# MotorDriver.net
KiCad netlist of a schematic drawn in EAGLE
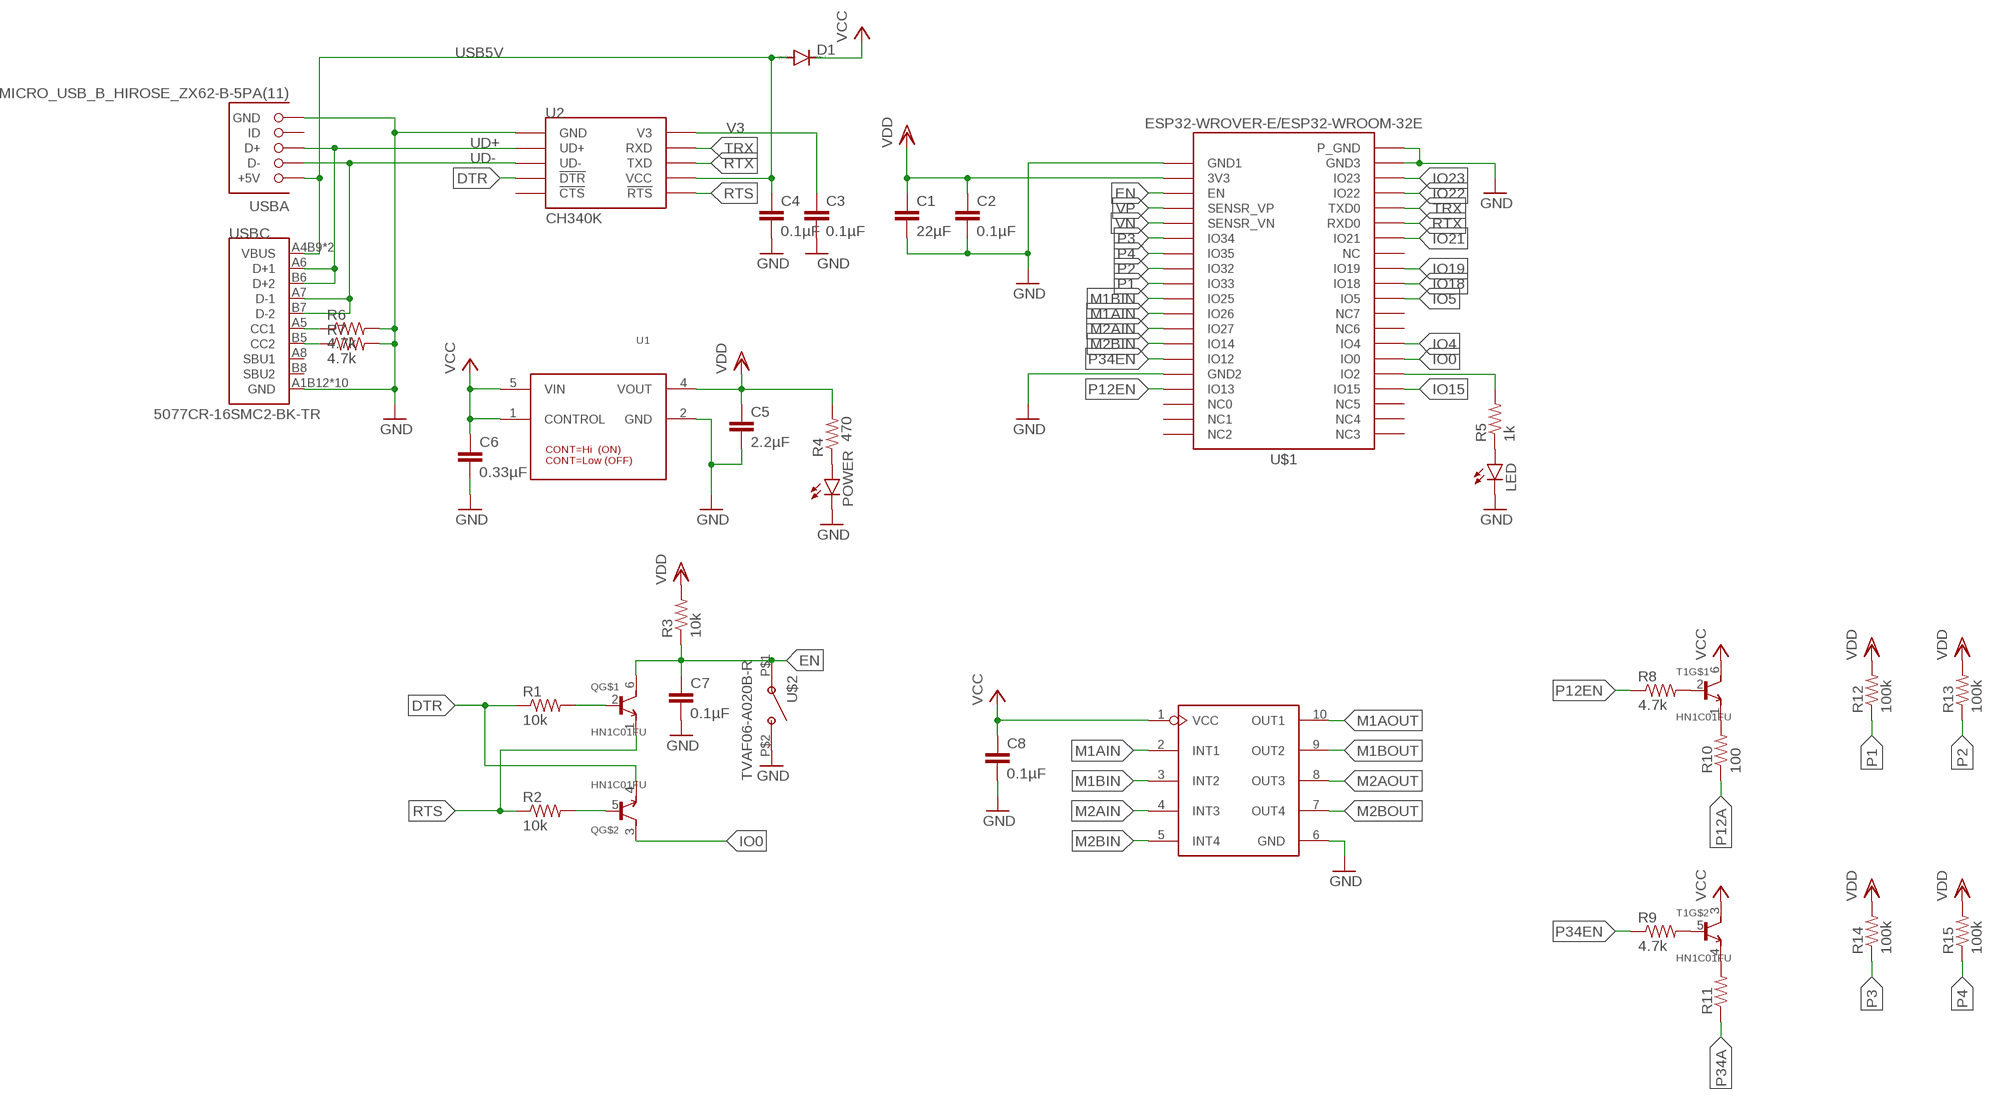
[diagram p0: schematic, sheet 1]

(export (version "E")
  (design (tool "Eeschema 10.0.6"))
  (components
    (comp (ref "C1")
      (value "22µF")
      (footprint "eagle-import:C0603K")
      (libsource (lib "eagle-import") (part "C-EUC0603K"))
    )
    (comp (ref "C2")
      (value "0.1µF")
      (footprint "eagle-import:C0603K")
      (libsource (lib "eagle-import") (part "C-EUC0603K"))
    )
    (comp (ref "C3")
      (value "0.1µF")
      (footprint "eagle-import:C0603K")
      (libsource (lib "eagle-import") (part "C-EUC0603K"))
    )
    (comp (ref "C4")
      (value "0.1µF")
      (footprint "eagle-import:C0603K")
      (libsource (lib "eagle-import") (part "C-EUC0603K"))
    )
    (comp (ref "C5")
      (value "2.2µF")
      (footprint "eagle-import:C0603K")
      (libsource (lib "eagle-import") (part "C-EUC0603K"))
    )
    (comp (ref "C6")
      (value "0.33µF")
      (footprint "eagle-import:C0603K")
      (libsource (lib "eagle-import") (part "C-EUC0603K"))
    )
    (comp (ref "C7")
      (value "0.1µF")
      (footprint "eagle-import:C0603K")
      (libsource (lib "eagle-import") (part "C-EUC0603K"))
    )
    (comp (ref "C8")
      (value "0.1µF")
      (footprint "eagle-import:C0603")
      (libsource (lib "eagle-import") (part "C-EUC0603"))
    )
    (comp (ref "D1")
      (value "DIODE-SOD123")
      (footprint "eagle-import:SOD123")
      (libsource (lib "eagle-import") (part "DIODE-SOD123"))
    )
    (comp (ref "LED")
      (value "LEDCHIPLED_0603")
      (footprint "eagle-import:CHIPLED_0603")
      (libsource (lib "eagle-import") (part "LEDCHIPLED_0603"))
    )
    (comp (ref "POWER")
      (value "LEDCHIPLED_0603")
      (footprint "eagle-import:CHIPLED_0603")
      (libsource (lib "eagle-import") (part "LEDCHIPLED_0603"))
    )
    (comp (ref "Q")
      (value "HN1C01FU")
      (footprint "eagle-import:SOT-363")
      (libsource (lib "eagle-import") (part "HN1C01FU"))
    )
    (comp (ref "R1")
      (value "10k")
      (footprint "eagle-import:R0603")
      (libsource (lib "eagle-import") (part "R-US_R0603"))
    )
    (comp (ref "R2")
      (value "10k")
      (footprint "eagle-import:R0603")
      (libsource (lib "eagle-import") (part "R-US_R0603"))
    )
    (comp (ref "R3")
      (value "10k")
      (footprint "eagle-import:R0603")
      (libsource (lib "eagle-import") (part "R-US_R0603"))
    )
    (comp (ref "R4")
      (value "470")
      (footprint "eagle-import:R0603")
      (libsource (lib "eagle-import") (part "R-US_R0603"))
    )
    (comp (ref "R5")
      (value "1k")
      (footprint "eagle-import:R0603")
      (libsource (lib "eagle-import") (part "R-US_R0603"))
    )
    (comp (ref "R6")
      (value "4.7k")
      (footprint "eagle-import:R0603")
      (libsource (lib "eagle-import") (part "R-US_R0603"))
    )
    (comp (ref "R7")
      (value "4.7k")
      (footprint "eagle-import:R0603")
      (libsource (lib "eagle-import") (part "R-US_R0603"))
    )
    (comp (ref "R8")
      (value "4.7k")
      (footprint "eagle-import:R0603")
      (libsource (lib "eagle-import") (part "R-US_R0603"))
    )
    (comp (ref "R9")
      (value "4.7k")
      (footprint "eagle-import:R0603")
      (libsource (lib "eagle-import") (part "R-US_R0603"))
    )
    (comp (ref "R10")
      (value "100")
      (footprint "eagle-import:R0603")
      (libsource (lib "eagle-import") (part "R-US_R0603"))
    )
    (comp (ref "R11")
      (value "R-US_R0603")
      (footprint "eagle-import:R0603")
      (libsource (lib "eagle-import") (part "R-US_R0603"))
    )
    (comp (ref "R12")
      (value "100k")
      (footprint "eagle-import:R0603")
      (libsource (lib "eagle-import") (part "R-US_R0603"))
    )
    (comp (ref "R13")
      (value "100k")
      (footprint "eagle-import:R0603")
      (libsource (lib "eagle-import") (part "R-US_R0603"))
    )
    (comp (ref "R14")
      (value "100k")
      (footprint "eagle-import:R0603")
      (libsource (lib "eagle-import") (part "R-US_R0603"))
    )
    (comp (ref "R15")
      (value "100k")
      (footprint "eagle-import:R0603")
      (libsource (lib "eagle-import") (part "R-US_R0603"))
    )
    (comp (ref "T1")
      (value "HN1C01FU")
      (footprint "eagle-import:SOT-363")
      (libsource (lib "eagle-import") (part "HN1C01FU"))
    )
    (comp (ref "U$1")
      (value "ESP32-WROVER-E/ESP32-WROOM-32E")
      (footprint "eagle-import:ESP32-WROVER-E_ESP32-WROOM-32E")
      (libsource (lib "eagle-import") (part "ESP32-WROVER-E/ESP32-WROOM-32E"))
    )
    (comp (ref "U$2")
      (value "TVAF06-A020B-R")
      (footprint "eagle-import:TVAF06-A020B-R")
      (libsource (lib "eagle-import") (part "TVAF06-A020B-R"))
    )
    (comp (ref "U1")
      (value "I-10673_NJM2884U1-33")
      (footprint "eagle-import:NJM2884U1-33")
      (libsource (lib "eagle-import") (part "I-10673_NJM2884U1-33"))
    )
    (comp (ref "U2")
      (value "CH340K")
      (footprint "eagle-import:ESSOP-10")
      (libsource (lib "eagle-import") (part "CH340K"))
    )
    (comp (ref "U3")
      (value "DRIVER-LV8548MC-AH(SOIC10)")
      (footprint "eagle-import:SOIC10-1.0-5X4MM")
      (fields (field (name "MF") "ON Semiconductor") (field (name "MP") "LV8548MC-AH"))
      (libsource (lib "eagle-import") (part "DRIVER-LV8548MC-AH(SOIC10)"))
    )
    (comp (ref "USBA")
      (value "MICRO_USB_B_HIROSE_ZX62-B-5PA(11)")
      (footprint "eagle-import:USB_MICRO_B-HIROSE-ZX62-B-5PA(11)")
      (libsource (lib "eagle-import") (part "MICRO_USB_B_HIROSE_ZX62-B-5PA(11)"))
    )
    (comp (ref "USBC")
      (value "5077CR-16SMC2-BK-TR")
      (footprint "eagle-import:5077CR-16SMC2-BK-TR")
      (libsource (lib "eagle-import") (part "5077CR-16SMC2-BK-TR"))
    )
  )
  (nets
    (net (code "1") (name "/UD+") (class "Default")
      (node (ref "U2") (pin "P1") (pinfunction "UD+_P1") (pintype "bidirectional"))
      (node (ref "USBA") (pin "3") (pinfunction "D+_3") (pintype "bidirectional"))
      (node (ref "USBC") (pin "A6") (pinfunction "D+1_A6") (pintype "bidirectional"))
      (node (ref "USBC") (pin "B6") (pinfunction "D+2_B6") (pintype "bidirectional"))
    )
    (net (code "2") (name "/UD-") (class "Default")
      (node (ref "U2") (pin "P2") (pinfunction "UD-_P2") (pintype "bidirectional"))
      (node (ref "USBA") (pin "2") (pinfunction "D-_2") (pintype "bidirectional"))
      (node (ref "USBC") (pin "A7") (pinfunction "D-1_A7") (pintype "bidirectional"))
      (node (ref "USBC") (pin "B7") (pinfunction "D-2_B7") (pintype "bidirectional"))
    )
    (net (code "3") (name "/USB5V") (class "Default")
      (node (ref "C4") (pin "1") (pinfunction "1_1") (pintype "passive"))
      (node (ref "D1") (pin "A") (pinfunction "A_A") (pintype "passive"))
      (node (ref "U2") (pin "P7") (pinfunction "VCC_P7") (pintype "power_in"))
      (node (ref "USBA") (pin "1") (pinfunction "+5V_1") (pintype "bidirectional"))
      (node (ref "USBC") (pin "A4B9") (pinfunction "VBUS_A4B9") (pintype "power_in"))
      (node (ref "USBC") (pin "B4A9") (pinfunction "VBUS_B4A9") (pintype "power_in"))
    )
    (net (code "4") (name "/V3") (class "Default")
      (node (ref "C3") (pin "1") (pinfunction "1_1") (pintype "passive"))
      (node (ref "U2") (pin "P10") (pinfunction "V3_P10") (pintype "power_in"))
    )
    (net (code "5") (name "DTR") (class "Default")
      (node (ref "Q") (pin "4") (pinfunction "E_4") (pintype "bidirectional"))
      (node (ref "R1") (pin "1") (pinfunction "1_1") (pintype "passive"))
      (node (ref "U2") (pin "P4") (pinfunction "~{DTR}_P4") (pintype "bidirectional"))
    )
    (net (code "6") (name "EN") (class "Default")
      (node (ref "C7") (pin "1") (pinfunction "1_1") (pintype "passive"))
      (node (ref "Q") (pin "6") (pinfunction "C_6") (pintype "bidirectional"))
      (node (ref "R3") (pin "1") (pinfunction "1_1") (pintype "passive"))
      (node (ref "U$1") (pin "EN") (pinfunction "EN_EN") (pintype "bidirectional"))
      (node (ref "U$2") (pin "P$1") (pinfunction "A_P$1") (pintype "bidirectional"))
    )
    (net (code "7") (name "GND") (class "Default")
      (node (ref "C1") (pin "2") (pinfunction "2_2") (pintype "passive"))
      (node (ref "C2") (pin "2") (pinfunction "2_2") (pintype "passive"))
      (node (ref "C3") (pin "2") (pinfunction "2_2") (pintype "passive"))
      (node (ref "C4") (pin "2") (pinfunction "2_2") (pintype "passive"))
      (node (ref "C5") (pin "2") (pinfunction "2_2") (pintype "passive"))
      (node (ref "C6") (pin "2") (pinfunction "2_2") (pintype "passive"))
      (node (ref "C7") (pin "2") (pinfunction "2_2") (pintype "passive"))
      (node (ref "C8") (pin "2") (pinfunction "2_2") (pintype "passive"))
      (node (ref "LED") (pin "C") (pinfunction "C_C") (pintype "passive"))
      (node (ref "POWER") (pin "C") (pinfunction "C_C") (pintype "passive"))
      (node (ref "R6") (pin "2") (pinfunction "2_2") (pintype "passive"))
      (node (ref "R7") (pin "2") (pinfunction "2_2") (pintype "passive"))
      (node (ref "U$1") (pin "GND1") (pinfunction "GND1_GND1") (pintype "power_in"))
      (node (ref "U$1") (pin "GND2") (pinfunction "GND2_GND2") (pintype "power_in"))
      (node (ref "U$1") (pin "GND2'") (pinfunction "GND2_GND2'") (pintype "power_in"))
      (node (ref "U$1") (pin "GND3") (pinfunction "GND3_GND3") (pintype "power_in"))
      (node (ref "U$1") (pin "P_GND") (pinfunction "P_GND_P_GND") (pintype "power_in"))
      (node (ref "U$2") (pin "P$2") (pinfunction "B_P$2") (pintype "bidirectional"))
      (node (ref "U1") (pin "2") (pinfunction "GND_2") (pintype "bidirectional"))
      (node (ref "U2") (pin "P0") (pinfunction "GND_P0") (pintype "power_in"))
      (node (ref "U2") (pin "P3") (pinfunction "GND_P3") (pintype "power_in"))
      (node (ref "U3") (pin "6") (pinfunction "GND_6") (pintype "bidirectional"))
      (node (ref "USBA") (pin "5") (pinfunction "GND_5") (pintype "bidirectional"))
      (node (ref "USBC") (pin "A1B12") (pinfunction "GND_A1B12") (pintype "power_in"))
      (node (ref "USBC") (pin "B1A12") (pinfunction "GND_B1A12") (pintype "power_in"))
      (node (ref "USBC") (pin "P$1") (pinfunction "GND_P$1") (pintype "power_in"))
      (node (ref "USBC") (pin "P$2") (pinfunction "GND_P$2") (pintype "power_in"))
      (node (ref "USBC") (pin "P$3") (pinfunction "GND_P$3") (pintype "power_in"))
      (node (ref "USBC") (pin "P$4") (pinfunction "GND_P$4") (pintype "power_in"))
      (node (ref "USBC") (pin "P$5") (pinfunction "GND_P$5") (pintype "power_in"))
      (node (ref "USBC") (pin "P$6") (pinfunction "GND_P$6") (pintype "power_in"))
      (node (ref "USBC") (pin "P$7") (pinfunction "GND_P$7") (pintype "power_in"))
      (node (ref "USBC") (pin "P$8") (pinfunction "GND_P$8") (pintype "power_in"))
    )
    (net (code "8") (name "IO0") (class "Default")
      (node (ref "Q") (pin "3") (pinfunction "C_3") (pintype "bidirectional"))
      (node (ref "U$1") (pin "IO0") (pinfunction "IO0_IO0") (pintype "bidirectional"))
    )
    (net (code "9") (name "IO4") (class "Default")
      (node (ref "U$1") (pin "IO4") (pinfunction "IO4_IO4") (pintype "bidirectional"))
    )
    (net (code "10") (name "IO5") (class "Default")
      (node (ref "U$1") (pin "IO5") (pinfunction "IO5_IO5") (pintype "bidirectional"))
    )
    (net (code "11") (name "IO15") (class "Default")
      (node (ref "U$1") (pin "IO15") (pinfunction "IO15_IO15") (pintype "bidirectional"))
      (node (ref "U$1") (pin "IO15'") (pinfunction "IO15_IO15'") (pintype "bidirectional"))
    )
    (net (code "12") (name "IO18") (class "Default")
      (node (ref "U$1") (pin "IO18") (pinfunction "IO18_IO18") (pintype "bidirectional"))
    )
    (net (code "13") (name "IO19") (class "Default")
      (node (ref "U$1") (pin "IO19") (pinfunction "IO19_IO19") (pintype "bidirectional"))
    )
    (net (code "14") (name "IO21") (class "Default")
      (node (ref "U$1") (pin "IO21") (pinfunction "IO21_IO21") (pintype "bidirectional"))
    )
    (net (code "15") (name "IO22") (class "Default")
      (node (ref "U$1") (pin "IO22") (pinfunction "IO22_IO22") (pintype "bidirectional"))
    )
    (net (code "16") (name "IO23") (class "Default")
      (node (ref "U$1") (pin "IO23") (pinfunction "IO23_IO23") (pintype "bidirectional"))
    )
    (net (code "17") (name "M1AIN") (class "Default")
      (node (ref "U$1") (pin "IO26") (pinfunction "IO26_IO26") (pintype "bidirectional"))
      (node (ref "U3") (pin "2") (pinfunction "INT1_2") (pintype "bidirectional"))
    )
    (net (code "18") (name "M1AOUT") (class "Default")
      (node (ref "U3") (pin "10") (pinfunction "OUT1_10") (pintype "bidirectional"))
    )
    (net (code "19") (name "M1BIN") (class "Default")
      (node (ref "U$1") (pin "IO25") (pinfunction "IO25_IO25") (pintype "bidirectional"))
      (node (ref "U3") (pin "3") (pinfunction "INT2_3") (pintype "bidirectional"))
    )
    (net (code "20") (name "M1BOUT") (class "Default")
      (node (ref "U3") (pin "9") (pinfunction "OUT2_9") (pintype "bidirectional"))
    )
    (net (code "21") (name "M2AIN") (class "Default")
      (node (ref "U$1") (pin "IO27") (pinfunction "IO27_IO27") (pintype "bidirectional"))
      (node (ref "U3") (pin "4") (pinfunction "INT3_4") (pintype "bidirectional"))
    )
    (net (code "22") (name "M2AOUT") (class "Default")
      (node (ref "U3") (pin "8") (pinfunction "OUT3_8") (pintype "bidirectional"))
    )
    (net (code "23") (name "M2BIN") (class "Default")
      (node (ref "U$1") (pin "IO14") (pinfunction "IO14_IO14") (pintype "bidirectional"))
      (node (ref "U3") (pin "5") (pinfunction "INT4_5") (pintype "bidirectional"))
    )
    (net (code "24") (name "M2BOUT") (class "Default")
      (node (ref "U3") (pin "7") (pinfunction "OUT4_7") (pintype "bidirectional"))
    )
    (net (code "25") (name "Net-(LED-PadA)") (class "Default")
      (node (ref "LED") (pin "A") (pinfunction "A_A") (pintype "passive"))
      (node (ref "R5") (pin "1") (pinfunction "1_1") (pintype "passive"))
    )
    (net (code "26") (name "Net-(POWER-PadA)") (class "Default")
      (node (ref "POWER") (pin "A") (pinfunction "A_A") (pintype "passive"))
      (node (ref "R4") (pin "1") (pinfunction "1_1") (pintype "passive"))
    )
    (net (code "27") (name "Net-(QA-B)") (class "Default")
      (node (ref "Q") (pin "2") (pinfunction "B_2") (pintype "bidirectional"))
      (node (ref "R1") (pin "2") (pinfunction "2_2") (pintype "passive"))
    )
    (net (code "28") (name "Net-(QB-B)") (class "Default")
      (node (ref "Q") (pin "5") (pinfunction "B_5") (pintype "bidirectional"))
      (node (ref "R2") (pin "2") (pinfunction "2_2") (pintype "passive"))
    )
    (net (code "29") (name "Net-(R5-Pad2)") (class "Default")
      (node (ref "R5") (pin "2") (pinfunction "2_2") (pintype "passive"))
      (node (ref "U$1") (pin "IO2") (pinfunction "IO2_IO2") (pintype "bidirectional"))
      (node (ref "U$1") (pin "IO2'") (pinfunction "IO2_IO2'") (pintype "bidirectional"))
    )
    (net (code "30") (name "Net-(T1A-B)") (class "Default")
      (node (ref "R8") (pin "2") (pinfunction "2_2") (pintype "passive"))
      (node (ref "T1") (pin "2") (pinfunction "B_2") (pintype "bidirectional"))
    )
    (net (code "31") (name "Net-(T1A-E)") (class "Default")
      (node (ref "R10") (pin "2") (pinfunction "2_2") (pintype "passive"))
      (node (ref "T1") (pin "1") (pinfunction "E_1") (pintype "bidirectional"))
    )
    (net (code "32") (name "Net-(T1B-B)") (class "Default")
      (node (ref "R9") (pin "2") (pinfunction "2_2") (pintype "passive"))
      (node (ref "T1") (pin "5") (pinfunction "B_5") (pintype "bidirectional"))
    )
    (net (code "33") (name "Net-(T1B-E)") (class "Default")
      (node (ref "R11") (pin "2") (pinfunction "2_2") (pintype "passive"))
      (node (ref "T1") (pin "4") (pinfunction "E_4") (pintype "bidirectional"))
    )
    (net (code "34") (name "Net-(USBC-CC1)") (class "Default")
      (node (ref "R6") (pin "1") (pinfunction "1_1") (pintype "passive"))
      (node (ref "USBC") (pin "A5") (pinfunction "CC1_A5") (pintype "bidirectional"))
    )
    (net (code "35") (name "Net-(USBC-CC2)") (class "Default")
      (node (ref "R7") (pin "1") (pinfunction "1_1") (pintype "passive"))
      (node (ref "USBC") (pin "B5") (pinfunction "CC2_B5") (pintype "bidirectional"))
    )
    (net (code "36") (name "P1") (class "Default")
      (node (ref "R12") (pin "1") (pinfunction "1_1") (pintype "passive"))
      (node (ref "U$1") (pin "IO33") (pinfunction "IO33_IO33") (pintype "bidirectional"))
    )
    (net (code "37") (name "P2") (class "Default")
      (node (ref "R13") (pin "1") (pinfunction "1_1") (pintype "passive"))
      (node (ref "U$1") (pin "IO32") (pinfunction "IO32_IO32") (pintype "bidirectional"))
    )
    (net (code "38") (name "P3") (class "Default")
      (node (ref "R14") (pin "1") (pinfunction "1_1") (pintype "passive"))
      (node (ref "U$1") (pin "IO34") (pinfunction "IO34_IO34") (pintype "bidirectional"))
    )
    (net (code "39") (name "P4") (class "Default")
      (node (ref "R15") (pin "1") (pinfunction "1_1") (pintype "passive"))
      (node (ref "U$1") (pin "IO35") (pinfunction "IO35_IO35") (pintype "bidirectional"))
    )
    (net (code "40") (name "P12A") (class "Default")
      (node (ref "R10") (pin "1") (pinfunction "1_1") (pintype "passive"))
    )
    (net (code "41") (name "P12EN") (class "Default")
      (node (ref "R8") (pin "1") (pinfunction "1_1") (pintype "passive"))
      (node (ref "U$1") (pin "IO13") (pinfunction "IO13_IO13") (pintype "bidirectional"))
      (node (ref "U$1") (pin "IO13'") (pinfunction "IO13_IO13'") (pintype "bidirectional"))
    )
    (net (code "42") (name "P34A") (class "Default")
      (node (ref "R11") (pin "1") (pinfunction "1_1") (pintype "passive"))
    )
    (net (code "43") (name "P34EN") (class "Default")
      (node (ref "R9") (pin "1") (pinfunction "1_1") (pintype "passive"))
      (node (ref "U$1") (pin "IO12") (pinfunction "IO12_IO12") (pintype "bidirectional"))
    )
    (net (code "44") (name "RTS") (class "Default")
      (node (ref "Q") (pin "1") (pinfunction "E_1") (pintype "bidirectional"))
      (node (ref "R2") (pin "1") (pinfunction "1_1") (pintype "passive"))
      (node (ref "U2") (pin "P6") (pinfunction "~{RTS}_P6") (pintype "bidirectional"))
    )
    (net (code "45") (name "RTX") (class "Default")
      (node (ref "U$1") (pin "RXD0") (pinfunction "RXD0_RXD0") (pintype "bidirectional"))
      (node (ref "U2") (pin "P8") (pinfunction "TXD_P8") (pintype "bidirectional"))
    )
    (net (code "46") (name "TRX") (class "Default")
      (node (ref "U$1") (pin "TXD0") (pinfunction "TXD0_TXD0") (pintype "bidirectional"))
      (node (ref "U2") (pin "P9") (pinfunction "RXD_P9") (pintype "bidirectional"))
    )
    (net (code "47") (name "VCC") (class "Default")
      (node (ref "C6") (pin "1") (pinfunction "1_1") (pintype "passive"))
      (node (ref "C8") (pin "1") (pinfunction "1_1") (pintype "passive"))
      (node (ref "D1") (pin "C") (pinfunction "C_C") (pintype "passive"))
      (node (ref "T1") (pin "3") (pinfunction "C_3") (pintype "bidirectional"))
      (node (ref "T1") (pin "6") (pinfunction "C_6") (pintype "bidirectional"))
      (node (ref "U1") (pin "1") (pinfunction "CONTROL_1") (pintype "bidirectional"))
      (node (ref "U1") (pin "5") (pinfunction "VIN_5") (pintype "bidirectional"))
      (node (ref "U3") (pin "1") (pinfunction "VCC_1") (pintype "bidirectional"))
    )
    (net (code "48") (name "VDD") (class "Default")
      (node (ref "C1") (pin "1") (pinfunction "1_1") (pintype "passive"))
      (node (ref "C2") (pin "1") (pinfunction "1_1") (pintype "passive"))
      (node (ref "C5") (pin "1") (pinfunction "1_1") (pintype "passive"))
      (node (ref "R12") (pin "2") (pinfunction "2_2") (pintype "passive"))
      (node (ref "R13") (pin "2") (pinfunction "2_2") (pintype "passive"))
      (node (ref "R14") (pin "2") (pinfunction "2_2") (pintype "passive"))
      (node (ref "R15") (pin "2") (pinfunction "2_2") (pintype "passive"))
      (node (ref "R3") (pin "2") (pinfunction "2_2") (pintype "passive"))
      (node (ref "R4") (pin "2") (pinfunction "2_2") (pintype "passive"))
      (node (ref "U$1") (pin "3V3") (pinfunction "3V3_3V3") (pintype "power_in"))
      (node (ref "U1") (pin "4") (pinfunction "VOUT_4") (pintype "bidirectional"))
    )
    (net (code "49") (name "VN") (class "Default")
      (node (ref "U$1") (pin "SENSOR_VN") (pinfunction "SENSR_VN_SENSOR_VN") (pintype "bidirectional"))
    )
    (net (code "50") (name "VP") (class "Default")
      (node (ref "U$1") (pin "SENSOR_VP") (pinfunction "SENSR_VP_SENSOR_VP") (pintype "bidirectional"))
    )
    (net (code "51") (name "unconnected-(U$1-NC0-PadNC0')") (class "Default")
      (node (ref "U$1") (pin "NC0'") (pinfunction "NC0_NC0'") (pintype "no_connect"))
    )
    (net (code "52") (name "unconnected-(U$1-NC1-PadNC1')") (class "Default")
      (node (ref "U$1") (pin "NC1'") (pinfunction "NC1_NC1'") (pintype "no_connect"))
    )
    (net (code "53") (name "unconnected-(U$1-NC2-PadNC2')") (class "Default")
      (node (ref "U$1") (pin "NC2'") (pinfunction "NC2_NC2'") (pintype "no_connect"))
    )
    (net (code "54") (name "unconnected-(U$1-NC3-PadNC3')") (class "Default")
      (node (ref "U$1") (pin "NC3'") (pinfunction "NC3_NC3'") (pintype "no_connect"))
    )
    (net (code "55") (name "unconnected-(U$1-NC4-PadNC4')") (class "Default")
      (node (ref "U$1") (pin "NC4'") (pinfunction "NC4_NC4'") (pintype "no_connect"))
    )
    (net (code "56") (name "unconnected-(U$1-NC5-PadNC5')") (class "Default")
      (node (ref "U$1") (pin "NC5'") (pinfunction "NC5_NC5'") (pintype "no_connect"))
    )
    (net (code "57") (name "unconnected-(U$1-NC6-PadIO16)") (class "Default")
      (node (ref "U$1") (pin "IO16") (pinfunction "NC6_IO16") (pintype "no_connect"))
    )
    (net (code "58") (name "unconnected-(U$1-NC7-PadIO17)") (class "Default")
      (node (ref "U$1") (pin "IO17") (pinfunction "NC7_IO17") (pintype "no_connect"))
    )
    (net (code "59") (name "unconnected-(U$1-PadNC)") (class "Default")
      (node (ref "U$1") (pin "NC") (pinfunction "NC_NC") (pintype "no_connect"))
    )
    (net (code "60") (name "unconnected-(U$1-PadNC0)") (class "Default")
      (node (ref "U$1") (pin "NC0") (pinfunction "NC0_NC0") (pintype "no_connect"))
    )
    (net (code "61") (name "unconnected-(U$1-PadNC1)") (class "Default")
      (node (ref "U$1") (pin "NC1") (pinfunction "NC1_NC1") (pintype "no_connect"))
    )
    (net (code "62") (name "unconnected-(U$1-PadNC2)") (class "Default")
      (node (ref "U$1") (pin "NC2") (pinfunction "NC2_NC2") (pintype "no_connect"))
    )
    (net (code "63") (name "unconnected-(U$1-PadNC3)") (class "Default")
      (node (ref "U$1") (pin "NC3") (pinfunction "NC3_NC3") (pintype "no_connect"))
    )
    (net (code "64") (name "unconnected-(U$1-PadNC4)") (class "Default")
      (node (ref "U$1") (pin "NC4") (pinfunction "NC4_NC4") (pintype "no_connect"))
    )
    (net (code "65") (name "unconnected-(U$1-PadNC5)") (class "Default")
      (node (ref "U$1") (pin "NC5") (pinfunction "NC5_NC5") (pintype "no_connect"))
    )
    (net (code "66") (name "unconnected-(U2-~{CTS}-PadP5)") (class "Default")
      (node (ref "U2") (pin "P5") (pinfunction "~{CTS}_P5") (pintype "bidirectional"))
    )
    (net (code "67") (name "unconnected-(USBA-ID-Pad4)") (class "Default")
      (node (ref "USBA") (pin "4") (pinfunction "ID_4") (pintype "bidirectional"))
    )
    (net (code "68") (name "unconnected-(USBC-SBU1-PadA8)") (class "Default")
      (node (ref "USBC") (pin "A8") (pinfunction "SBU1_A8") (pintype "bidirectional"))
    )
    (net (code "69") (name "unconnected-(USBC-SBU2-PadB8)") (class "Default")
      (node (ref "USBC") (pin "B8") (pinfunction "SBU2_B8") (pintype "bidirectional"))
    )
  )
)
